# displayshield_v1.net
KiCad netlist of a schematic drawn in EAGLE
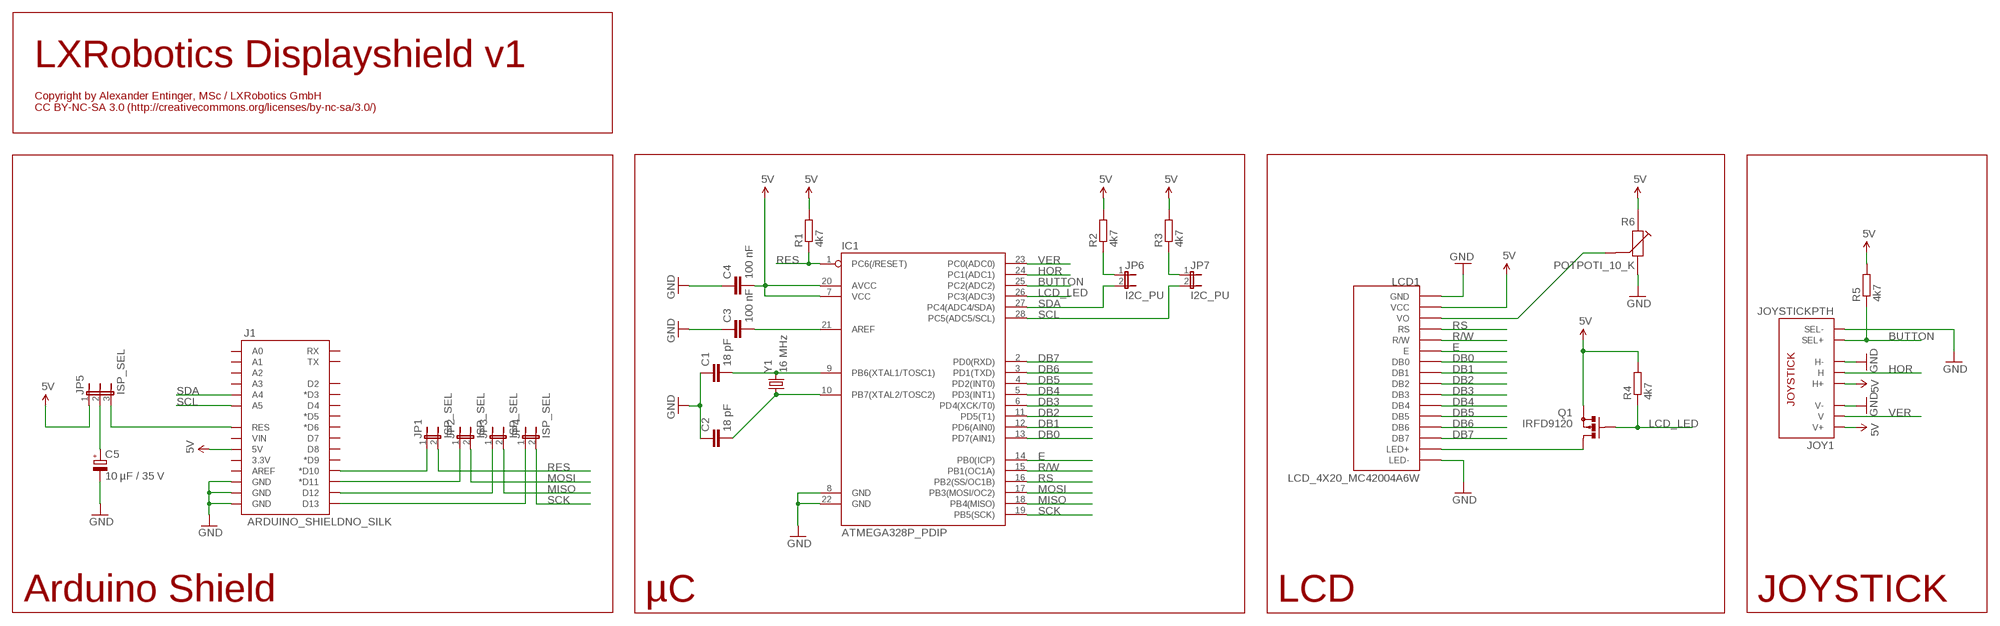
[diagram p0: schematic, sheet 1]

(export (version "E")
  (design (tool "Eeschema 10.0.6"))
  (components
    (comp (ref "C1")
      (value "18 pF")
      (footprint "eagle-import:C025-025X050")
      (libsource (lib "eagle-import") (part "C-EU025-025X050"))
    )
    (comp (ref "C2")
      (value "18 pF")
      (footprint "eagle-import:C025-025X050")
      (libsource (lib "eagle-import") (part "C-EU025-025X050"))
    )
    (comp (ref "C3")
      (value "100 nF")
      (footprint "eagle-import:C025-025X050")
      (libsource (lib "eagle-import") (part "C-EU025-025X050"))
    )
    (comp (ref "C4")
      (value "100 nF")
      (footprint "eagle-import:C025-025X050")
      (libsource (lib "eagle-import") (part "C-EU025-025X050"))
    )
    (comp (ref "C5")
      (value "10 µF / 35 V")
      (footprint "eagle-import:E2-5")
      (libsource (lib "eagle-import") (part "CPOL-EUE2-5"))
    )
    (comp (ref "IC1")
      (value "ATMEGA328P_PDIP")
      (footprint "eagle-import:DIL28-3")
      (libsource (lib "eagle-import") (part "ATMEGA328P_PDIP"))
    )
    (comp (ref "J1")
      (value "ARDUINO_SHIELDNO_SILK")
      (footprint "eagle-import:DUEMILANOVE_VIAS")
      (libsource (lib "eagle-import") (part "ARDUINO_SHIELDNO_SILK"))
    )
    (comp (ref "JOY1")
      (value "JOYSTICKPTH")
      (footprint "eagle-import:JOYSTICK")
      (libsource (lib "eagle-import") (part "JOYSTICKPTH"))
    )
    (comp (ref "JP1")
      (value "ISP_SEL")
      (footprint "eagle-import:JP1")
      (libsource (lib "eagle-import") (part "JP1E"))
    )
    (comp (ref "JP2")
      (value "ISP_SEL")
      (footprint "eagle-import:JP1")
      (libsource (lib "eagle-import") (part "JP1E"))
    )
    (comp (ref "JP3")
      (value "ISP_SEL")
      (footprint "eagle-import:JP1")
      (libsource (lib "eagle-import") (part "JP1E"))
    )
    (comp (ref "JP4")
      (value "ISP_SEL")
      (footprint "eagle-import:JP1")
      (libsource (lib "eagle-import") (part "JP1E"))
    )
    (comp (ref "JP5")
      (value "ISP_SEL")
      (footprint "eagle-import:JP2")
      (libsource (lib "eagle-import") (part "JP2E"))
    )
    (comp (ref "JP6")
      (value "I2C_PU")
      (footprint "eagle-import:JP1")
      (libsource (lib "eagle-import") (part "JP1E"))
    )
    (comp (ref "JP7")
      (value "I2C_PU")
      (footprint "eagle-import:JP1")
      (libsource (lib "eagle-import") (part "JP1E"))
    )
    (comp (ref "LCD1")
      (value "LCD_4X20_MC42004A6W")
      (footprint "eagle-import:LCD_3X40_MC42004A6W")
      (libsource (lib "eagle-import") (part "LCD_4X20_MC42004A6W"))
    )
    (comp (ref "Q1")
      (value "IRFD9120")
      (footprint "eagle-import:C370-01")
      (libsource (lib "eagle-import") (part "IRFD9120"))
    )
    (comp (ref "R1")
      (value "4k7")
      (footprint "eagle-import:0204_5")
      (libsource (lib "eagle-import") (part "R-EU_0204/5"))
    )
    (comp (ref "R2")
      (value "4k7")
      (footprint "eagle-import:0204_5")
      (libsource (lib "eagle-import") (part "R-EU_0204/5"))
    )
    (comp (ref "R3")
      (value "4k7")
      (footprint "eagle-import:0204_5")
      (libsource (lib "eagle-import") (part "R-EU_0204/5"))
    )
    (comp (ref "R4")
      (value "4k7")
      (footprint "eagle-import:0204_5")
      (libsource (lib "eagle-import") (part "R-EU_0204/5"))
    )
    (comp (ref "R5")
      (value "4k7")
      (footprint "eagle-import:0204_5")
      (libsource (lib "eagle-import") (part "R-EU_0204/5"))
    )
    (comp (ref "R6")
      (value "POTPOTI_10_K")
      (footprint "eagle-import:POT_10K")
      (libsource (lib "eagle-import") (part "POTPOTI_10_K"))
    )
    (comp (ref "Y1")
      (value "16 MHz")
      (footprint "eagle-import:HC49US")
      (libsource (lib "eagle-import") (part "CRYSTALHC49US"))
    )
  )
  (nets
    (net (code "1") (name "/BUTTON") (class "Default")
      (node (ref "IC1") (pin "25") (pinfunction "PC2(ADC2)_25") (pintype "bidirectional"))
      (node (ref "JOY1") (pin "B1A") (pinfunction "SEL+_B1A") (pintype "bidirectional"))
      (node (ref "R5") (pin "1") (pinfunction "1_1") (pintype "passive"))
    )
    (net (code "2") (name "/DB0") (class "Default")
      (node (ref "IC1") (pin "13") (pinfunction "PD7(AIN1)_13") (pintype "bidirectional"))
      (node (ref "LCD1") (pin "DB0") (pinfunction "DB0_DB0") (pintype "bidirectional"))
    )
    (net (code "3") (name "/DB1") (class "Default")
      (node (ref "IC1") (pin "12") (pinfunction "PD6(AIN0)_12") (pintype "bidirectional"))
      (node (ref "LCD1") (pin "DB1") (pinfunction "DB1_DB1") (pintype "bidirectional"))
    )
    (net (code "4") (name "/DB2") (class "Default")
      (node (ref "IC1") (pin "11") (pinfunction "PD5(T1)_11") (pintype "bidirectional"))
      (node (ref "LCD1") (pin "DB2") (pinfunction "DB2_DB2") (pintype "bidirectional"))
    )
    (net (code "5") (name "/DB3") (class "Default")
      (node (ref "IC1") (pin "6") (pinfunction "PD4(XCK/T0)_6") (pintype "bidirectional"))
      (node (ref "LCD1") (pin "DB3") (pinfunction "DB3_DB3") (pintype "bidirectional"))
    )
    (net (code "6") (name "/DB4") (class "Default")
      (node (ref "IC1") (pin "5") (pinfunction "PD3(INT1)_5") (pintype "bidirectional"))
      (node (ref "LCD1") (pin "DB4") (pinfunction "DB4_DB4") (pintype "bidirectional"))
    )
    (net (code "7") (name "/DB5") (class "Default")
      (node (ref "IC1") (pin "4") (pinfunction "PD2(INT0)_4") (pintype "bidirectional"))
      (node (ref "LCD1") (pin "DB5") (pinfunction "DB5_DB5") (pintype "bidirectional"))
    )
    (net (code "8") (name "/DB6") (class "Default")
      (node (ref "IC1") (pin "3") (pinfunction "PD1(TXD)_3") (pintype "bidirectional"))
      (node (ref "LCD1") (pin "DB6") (pinfunction "DB6_DB6") (pintype "bidirectional"))
    )
    (net (code "9") (name "/DB7") (class "Default")
      (node (ref "IC1") (pin "2") (pinfunction "PD0(RXD)_2") (pintype "bidirectional"))
      (node (ref "LCD1") (pin "DB7") (pinfunction "DB7_DB7") (pintype "bidirectional"))
    )
    (net (code "10") (name "/E") (class "Default")
      (node (ref "IC1") (pin "14") (pinfunction "PB0(ICP)_14") (pintype "bidirectional"))
      (node (ref "LCD1") (pin "E") (pinfunction "E_E") (pintype "bidirectional"))
    )
    (net (code "11") (name "/HOR") (class "Default")
      (node (ref "IC1") (pin "24") (pinfunction "PC1(ADC1)_24") (pintype "bidirectional"))
      (node (ref "JOY1") (pin "H2") (pinfunction "H_H2") (pintype "bidirectional"))
    )
    (net (code "12") (name "/LCD_LED") (class "Default")
      (node (ref "IC1") (pin "26") (pinfunction "PC3(ADC3)_26") (pintype "bidirectional"))
      (node (ref "Q1") (pin "G") (pinfunction "G_G") (pintype "passive"))
      (node (ref "R4") (pin "1") (pinfunction "1_1") (pintype "passive"))
    )
    (net (code "13") (name "/MISO") (class "Default")
      (node (ref "IC1") (pin "18") (pinfunction "PB4(MISO)_18") (pintype "bidirectional"))
      (node (ref "JP3") (pin "2") (pinfunction "2_2") (pintype "passive"))
    )
    (net (code "14") (name "/MOSI") (class "Default")
      (node (ref "IC1") (pin "17") (pinfunction "PB3(MOSI/OC2)_17") (pintype "bidirectional"))
      (node (ref "JP2") (pin "2") (pinfunction "2_2") (pintype "passive"))
    )
    (net (code "15") (name "/RES") (class "Default")
      (node (ref "IC1") (pin "1") (pinfunction "PC6(/RESET)_1") (pintype "bidirectional"))
      (node (ref "JP1") (pin "2") (pinfunction "2_2") (pintype "passive"))
      (node (ref "R1") (pin "1") (pinfunction "1_1") (pintype "passive"))
    )
    (net (code "16") (name "/RS") (class "Default")
      (node (ref "IC1") (pin "16") (pinfunction "PB2(SS/OC1B)_16") (pintype "bidirectional"))
      (node (ref "LCD1") (pin "RS") (pinfunction "RS_RS") (pintype "bidirectional"))
    )
    (net (code "17") (name "/R{slash}W") (class "Default")
      (node (ref "IC1") (pin "15") (pinfunction "PB1(OC1A)_15") (pintype "bidirectional"))
      (node (ref "LCD1") (pin "R/W") (pinfunction "R/W_R/W") (pintype "bidirectional"))
    )
    (net (code "18") (name "/SCK") (class "Default")
      (node (ref "IC1") (pin "19") (pinfunction "PB5(SCK)_19") (pintype "bidirectional"))
      (node (ref "JP4") (pin "2") (pinfunction "2_2") (pintype "passive"))
    )
    (net (code "19") (name "/SCL") (class "Default")
      (node (ref "IC1") (pin "28") (pinfunction "PC5(ADC5/SCL)_28") (pintype "bidirectional"))
      (node (ref "J1") (pin "A5") (pinfunction "A5_A5") (pintype "bidirectional"))
      (node (ref "JP7") (pin "2") (pinfunction "2_2") (pintype "passive"))
    )
    (net (code "20") (name "/SDA") (class "Default")
      (node (ref "IC1") (pin "27") (pinfunction "PC4(ADC4/SDA)_27") (pintype "bidirectional"))
      (node (ref "J1") (pin "A4") (pinfunction "A4_A4") (pintype "bidirectional"))
      (node (ref "JP6") (pin "2") (pinfunction "2_2") (pintype "passive"))
    )
    (net (code "21") (name "/VER") (class "Default")
      (node (ref "IC1") (pin "23") (pinfunction "PC0(ADC0)_23") (pintype "bidirectional"))
      (node (ref "JOY1") (pin "V2") (pinfunction "V_V2") (pintype "bidirectional"))
    )
    (net (code "22") (name "5V") (class "Default")
      (node (ref "C4") (pin "2") (pinfunction "2_2") (pintype "passive"))
      (node (ref "IC1") (pin "20") (pinfunction "AVCC_20") (pintype "bidirectional"))
      (node (ref "IC1") (pin "7") (pinfunction "VCC_7") (pintype "bidirectional"))
      (node (ref "J1") (pin "5V") (pinfunction "5V_5V") (pintype "bidirectional"))
      (node (ref "JOY1") (pin "H1") (pinfunction "H+_H1") (pintype "bidirectional"))
      (node (ref "JOY1") (pin "V1") (pinfunction "V+_V1") (pintype "bidirectional"))
      (node (ref "JP5") (pin "1") (pinfunction "1_1") (pintype "passive"))
      (node (ref "LCD1") (pin "VCC") (pinfunction "VCC_VCC") (pintype "bidirectional"))
      (node (ref "Q1") (pin "S") (pinfunction "S_S") (pintype "passive"))
      (node (ref "R1") (pin "2") (pinfunction "2_2") (pintype "passive"))
      (node (ref "R2") (pin "2") (pinfunction "2_2") (pintype "passive"))
      (node (ref "R3") (pin "2") (pinfunction "2_2") (pintype "passive"))
      (node (ref "R4") (pin "2") (pinfunction "2_2") (pintype "passive"))
      (node (ref "R5") (pin "2") (pinfunction "2_2") (pintype "passive"))
      (node (ref "R6") (pin "S") (pinfunction "S_S") (pintype "bidirectional"))
    )
    (net (code "23") (name "GND") (class "Default")
      (node (ref "C1") (pin "1") (pinfunction "1_1") (pintype "passive"))
      (node (ref "C2") (pin "1") (pinfunction "1_1") (pintype "passive"))
      (node (ref "C3") (pin "1") (pinfunction "1_1") (pintype "passive"))
      (node (ref "C4") (pin "1") (pinfunction "1_1") (pintype "passive"))
      (node (ref "C5") (pin "-") (pinfunction "-_-") (pintype "passive"))
      (node (ref "IC1") (pin "22") (pinfunction "GND_22") (pintype "bidirectional"))
      (node (ref "IC1") (pin "8") (pinfunction "GND_8") (pintype "bidirectional"))
      (node (ref "J1") (pin "GND@0") (pinfunction "GND_GND@0") (pintype "bidirectional"))
      (node (ref "J1") (pin "GND@1") (pinfunction "GND_GND@1") (pintype "bidirectional"))
      (node (ref "J1") (pin "GND@2") (pinfunction "GND_GND@2") (pintype "bidirectional"))
      (node (ref "JOY1") (pin "B2A") (pinfunction "SEL-_B2A") (pintype "bidirectional"))
      (node (ref "JOY1") (pin "H3") (pinfunction "H-_H3") (pintype "bidirectional"))
      (node (ref "JOY1") (pin "V3") (pinfunction "V-_V3") (pintype "bidirectional"))
      (node (ref "LCD1") (pin "GND") (pinfunction "GND_GND") (pintype "bidirectional"))
      (node (ref "LCD1") (pin "LED-") (pinfunction "LED-_LED-") (pintype "bidirectional"))
      (node (ref "R6") (pin "E") (pinfunction "E_E") (pintype "bidirectional"))
    )
    (net (code "24") (name "Net-(C5-Pad+)") (class "Default")
      (node (ref "C5") (pin "+") (pinfunction "+_+") (pintype "passive"))
      (node (ref "JP5") (pin "2") (pinfunction "2_2") (pintype "passive"))
    )
    (net (code "25") (name "Net-(IC1-AREF)") (class "Default")
      (node (ref "C3") (pin "2") (pinfunction "2_2") (pintype "passive"))
      (node (ref "IC1") (pin "21") (pinfunction "AREF_21") (pintype "bidirectional"))
    )
    (net (code "26") (name "Net-(IC1-PB6(XTAL1{slash}TOSC1))") (class "Default")
      (node (ref "C1") (pin "2") (pinfunction "2_2") (pintype "passive"))
      (node (ref "IC1") (pin "9") (pinfunction "PB6(XTAL1/TOSC1)_9") (pintype "bidirectional"))
      (node (ref "Y1") (pin "2") (pinfunction "2_2") (pintype "passive"))
    )
    (net (code "27") (name "Net-(IC1-PB7(XTAL2{slash}TOSC2))") (class "Default")
      (node (ref "C2") (pin "2") (pinfunction "2_2") (pintype "passive"))
      (node (ref "IC1") (pin "10") (pinfunction "PB7(XTAL2/TOSC2)_10") (pintype "bidirectional"))
      (node (ref "Y1") (pin "1") (pinfunction "1_1") (pintype "passive"))
    )
    (net (code "28") (name "Net-(J1-*D10)") (class "Default")
      (node (ref "J1") (pin "D10") (pinfunction "*D10_D10") (pintype "bidirectional"))
      (node (ref "JP1") (pin "1") (pinfunction "1_1") (pintype "passive"))
    )
    (net (code "29") (name "Net-(J1-*D11)") (class "Default")
      (node (ref "J1") (pin "D11") (pinfunction "*D11_D11") (pintype "bidirectional"))
      (node (ref "JP2") (pin "1") (pinfunction "1_1") (pintype "passive"))
    )
    (net (code "30") (name "Net-(J1-PadD12)") (class "Default")
      (node (ref "J1") (pin "D12") (pinfunction "D12_D12") (pintype "bidirectional"))
      (node (ref "JP3") (pin "1") (pinfunction "1_1") (pintype "passive"))
    )
    (net (code "31") (name "Net-(J1-PadD13)") (class "Default")
      (node (ref "J1") (pin "D13") (pinfunction "D13_D13") (pintype "bidirectional"))
      (node (ref "JP4") (pin "1") (pinfunction "1_1") (pintype "passive"))
    )
    (net (code "32") (name "Net-(J1-PadRES)") (class "Default")
      (node (ref "J1") (pin "RES") (pinfunction "RES_RES") (pintype "bidirectional"))
      (node (ref "JP5") (pin "3") (pinfunction "3_3") (pintype "passive"))
    )
    (net (code "33") (name "Net-(JP6-Pad1)") (class "Default")
      (node (ref "JP6") (pin "1") (pinfunction "1_1") (pintype "passive"))
      (node (ref "R2") (pin "1") (pinfunction "1_1") (pintype "passive"))
    )
    (net (code "34") (name "Net-(JP7-Pad1)") (class "Default")
      (node (ref "JP7") (pin "1") (pinfunction "1_1") (pintype "passive"))
      (node (ref "R3") (pin "1") (pinfunction "1_1") (pintype "passive"))
    )
    (net (code "35") (name "Net-(LCD1-PadLED+)") (class "Default")
      (node (ref "LCD1") (pin "LED+") (pinfunction "LED+_LED+") (pintype "bidirectional"))
      (node (ref "Q1") (pin "D") (pinfunction "D_D") (pintype "passive"))
      (node (ref "Q1") (pin "D1") (pinfunction "D_D1") (pintype "passive"))
    )
    (net (code "36") (name "Net-(LCD1-PadVO)") (class "Default")
      (node (ref "LCD1") (pin "VO") (pinfunction "VO_VO") (pintype "bidirectional"))
      (node (ref "R6") (pin "VAR") (pinfunction "VAR_VAR") (pintype "bidirectional"))
    )
    (net (code "37") (name "unconnected-(J1-*D3-PadD3)") (class "Default")
      (node (ref "J1") (pin "D3") (pinfunction "*D3_D3") (pintype "bidirectional"))
    )
    (net (code "38") (name "unconnected-(J1-*D5-PadD5)") (class "Default")
      (node (ref "J1") (pin "D5") (pinfunction "*D5_D5") (pintype "bidirectional"))
    )
    (net (code "39") (name "unconnected-(J1-*D6-PadD6)") (class "Default")
      (node (ref "J1") (pin "D6") (pinfunction "*D6_D6") (pintype "bidirectional"))
    )
    (net (code "40") (name "unconnected-(J1-*D9-PadD9)") (class "Default")
      (node (ref "J1") (pin "D9") (pinfunction "*D9_D9") (pintype "bidirectional"))
    )
    (net (code "41") (name "unconnected-(J1-Pad3.3V)") (class "Default")
      (node (ref "J1") (pin "3.3V") (pinfunction "3.3V_3.3V") (pintype "bidirectional"))
    )
    (net (code "42") (name "unconnected-(J1-PadA0)") (class "Default")
      (node (ref "J1") (pin "A0") (pinfunction "A0_A0") (pintype "bidirectional"))
    )
    (net (code "43") (name "unconnected-(J1-PadA1)") (class "Default")
      (node (ref "J1") (pin "A1") (pinfunction "A1_A1") (pintype "bidirectional"))
    )
    (net (code "44") (name "unconnected-(J1-PadA2)") (class "Default")
      (node (ref "J1") (pin "A2") (pinfunction "A2_A2") (pintype "bidirectional"))
    )
    (net (code "45") (name "unconnected-(J1-PadA3)") (class "Default")
      (node (ref "J1") (pin "A3") (pinfunction "A3_A3") (pintype "bidirectional"))
    )
    (net (code "46") (name "unconnected-(J1-PadAREF)") (class "Default")
      (node (ref "J1") (pin "AREF") (pinfunction "AREF_AREF") (pintype "bidirectional"))
    )
    (net (code "47") (name "unconnected-(J1-PadD2)") (class "Default")
      (node (ref "J1") (pin "D2") (pinfunction "D2_D2") (pintype "bidirectional"))
    )
    (net (code "48") (name "unconnected-(J1-PadD4)") (class "Default")
      (node (ref "J1") (pin "D4") (pinfunction "D4_D4") (pintype "bidirectional"))
    )
    (net (code "49") (name "unconnected-(J1-PadD7)") (class "Default")
      (node (ref "J1") (pin "D7") (pinfunction "D7_D7") (pintype "bidirectional"))
    )
    (net (code "50") (name "unconnected-(J1-PadD8)") (class "Default")
      (node (ref "J1") (pin "D8") (pinfunction "D8_D8") (pintype "bidirectional"))
    )
    (net (code "51") (name "unconnected-(J1-PadRX)") (class "Default")
      (node (ref "J1") (pin "RX") (pinfunction "RX_RX") (pintype "bidirectional"))
    )
    (net (code "52") (name "unconnected-(J1-PadTX)") (class "Default")
      (node (ref "J1") (pin "TX") (pinfunction "TX_TX") (pintype "bidirectional"))
    )
    (net (code "53") (name "unconnected-(J1-PadVIN)") (class "Default")
      (node (ref "J1") (pin "VIN") (pinfunction "VIN_VIN") (pintype "bidirectional"))
    )
  )
)
